# LED.net
KiCad netlist of a schematic drawn in EAGLE
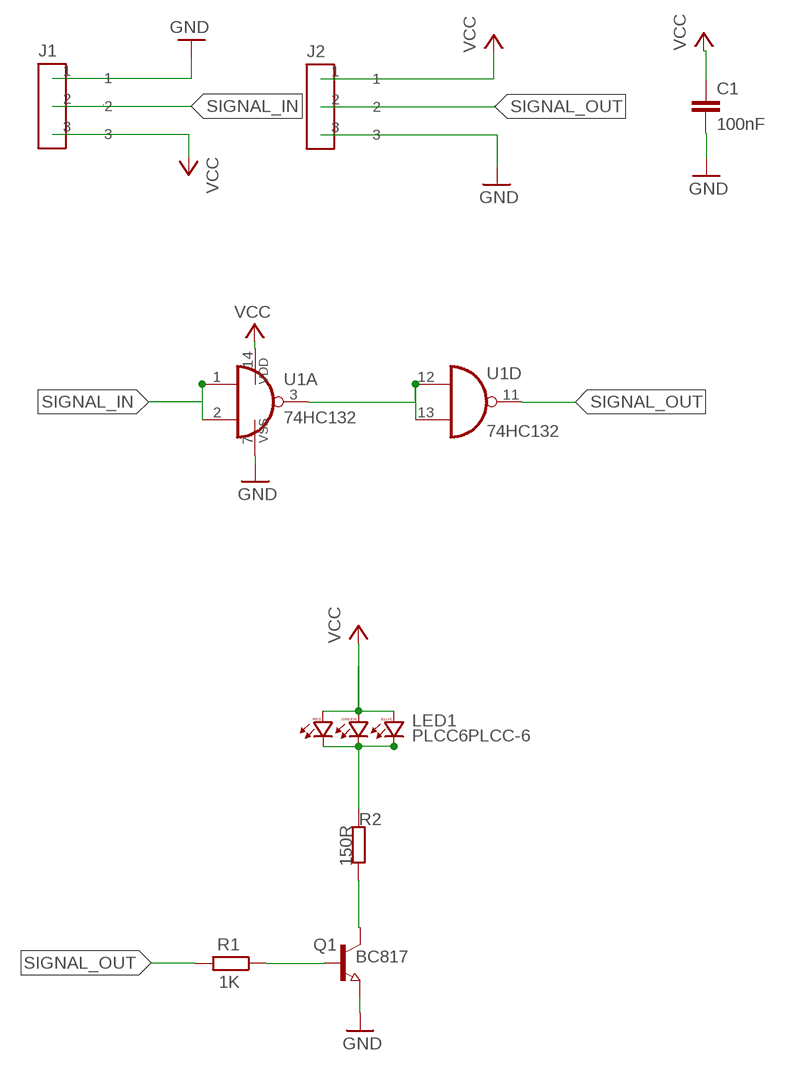
[diagram p0: schematic, sheet 1]

(export (version "E")
  (design (tool "Eeschema 10.0.6"))
  (components
    (comp (ref "C1")
      (value "100nF")
      (footprint "eagle-import:C0805")
      (libsource (lib "eagle-import") (part "C-EUC0805"))
    )
    (comp (ref "J1")
      (value "CONECTOR_MACHO")
      (footprint "eagle-import:3CONECTOR")
      (libsource (lib "eagle-import") (part "CONECTOR_MACHO"))
    )
    (comp (ref "J2")
      (value "CONECTOR_FEMEA")
      (footprint "eagle-import:3CONECTOR")
      (libsource (lib "eagle-import") (part "CONECTOR_FEMEA"))
    )
    (comp (ref "LED1")
      (value "PLCC6PLCC-6")
      (footprint "eagle-import:PLCC-6-LED")
      (libsource (lib "eagle-import") (part "PLCC6PLCC-6"))
    )
    (comp (ref "Q1")
      (value "BC817")
      (footprint "eagle-import:SOT23")
      (libsource (lib "eagle-import") (part "NPN-TRANSISTOR_SOT23"))
    )
    (comp (ref "R1")
      (value "1K")
      (footprint "eagle-import:R0805W")
      (libsource (lib "eagle-import") (part "R-EU_R0805W"))
    )
    (comp (ref "R2")
      (value "150R")
      (footprint "eagle-import:R0805W")
      (libsource (lib "eagle-import") (part "R-EU_R0805W"))
    )
    (comp (ref "U1")
      (value "74HC132")
      (footprint "eagle-import:SO14")
      (libsource (lib "eagle-import") (part "4011D"))
    )
  )
  (nets
    (net (code "1") (name "GND") (class "Default")
      (node (ref "C1") (pin "2") (pinfunction "2_2") (pintype "passive"))
      (node (ref "J1") (pin "1") (pinfunction "1_1") (pintype "bidirectional"))
      (node (ref "J2") (pin "3") (pinfunction "3_3") (pintype "bidirectional"))
      (node (ref "Q1") (pin "2") (pinfunction "E_2") (pintype "passive"))
      (node (ref "U1") (pin "7") (pinfunction "VSS_7") (pintype "power_in"))
    )
    (net (code "2") (name "Net-(LED1-BC)") (class "Default")
      (node (ref "LED1") (pin "CB") (pinfunction "BC_CB") (pintype "passive"))
      (node (ref "LED1") (pin "CG") (pinfunction "GC_CG") (pintype "passive"))
      (node (ref "LED1") (pin "CR") (pinfunction "RC_CR") (pintype "passive"))
      (node (ref "R2") (pin "2") (pinfunction "2_2") (pintype "passive"))
    )
    (net (code "3") (name "Net-(Q1-B)") (class "Default")
      (node (ref "Q1") (pin "1") (pinfunction "B_1") (pintype "passive"))
      (node (ref "R1") (pin "1") (pinfunction "1_1") (pintype "passive"))
    )
    (net (code "4") (name "Net-(Q1-C)") (class "Default")
      (node (ref "Q1") (pin "3") (pinfunction "C_3") (pintype "passive"))
      (node (ref "R2") (pin "1") (pinfunction "1_1") (pintype "passive"))
    )
    (net (code "5") (name "Net-(U1A-O)") (class "Default")
      (node (ref "U1") (pin "12") (pinfunction "I0_12") (pintype "input"))
      (node (ref "U1") (pin "13") (pinfunction "I1_13") (pintype "input"))
      (node (ref "U1") (pin "3") (pinfunction "O_3") (pintype "output"))
    )
    (net (code "6") (name "SIGNAL_IN") (class "Default")
      (node (ref "J1") (pin "2") (pinfunction "2_2") (pintype "bidirectional"))
      (node (ref "U1") (pin "1") (pinfunction "I0_1") (pintype "input"))
      (node (ref "U1") (pin "2") (pinfunction "I1_2") (pintype "input"))
    )
    (net (code "7") (name "SIGNAL_OUT") (class "Default")
      (node (ref "J2") (pin "2") (pinfunction "2_2") (pintype "bidirectional"))
      (node (ref "R1") (pin "2") (pinfunction "2_2") (pintype "passive"))
      (node (ref "U1") (pin "11") (pinfunction "O_11") (pintype "output"))
    )
    (net (code "8") (name "VCC") (class "Default")
      (node (ref "C1") (pin "1") (pinfunction "1_1") (pintype "passive"))
      (node (ref "J1") (pin "3") (pinfunction "3_3") (pintype "bidirectional"))
      (node (ref "J2") (pin "1") (pinfunction "1_1") (pintype "bidirectional"))
      (node (ref "LED1") (pin "AB") (pinfunction "BA_AB") (pintype "passive"))
      (node (ref "LED1") (pin "AG") (pinfunction "GA_AG") (pintype "passive"))
      (node (ref "LED1") (pin "AR") (pinfunction "RA_AR") (pintype "passive"))
      (node (ref "U1") (pin "14") (pinfunction "VDD_14") (pintype "power_in"))
    )
  )
)
